# STM32G473CET6_PINOUT.net
KiCad netlist of a schematic drawn in Altium Designer
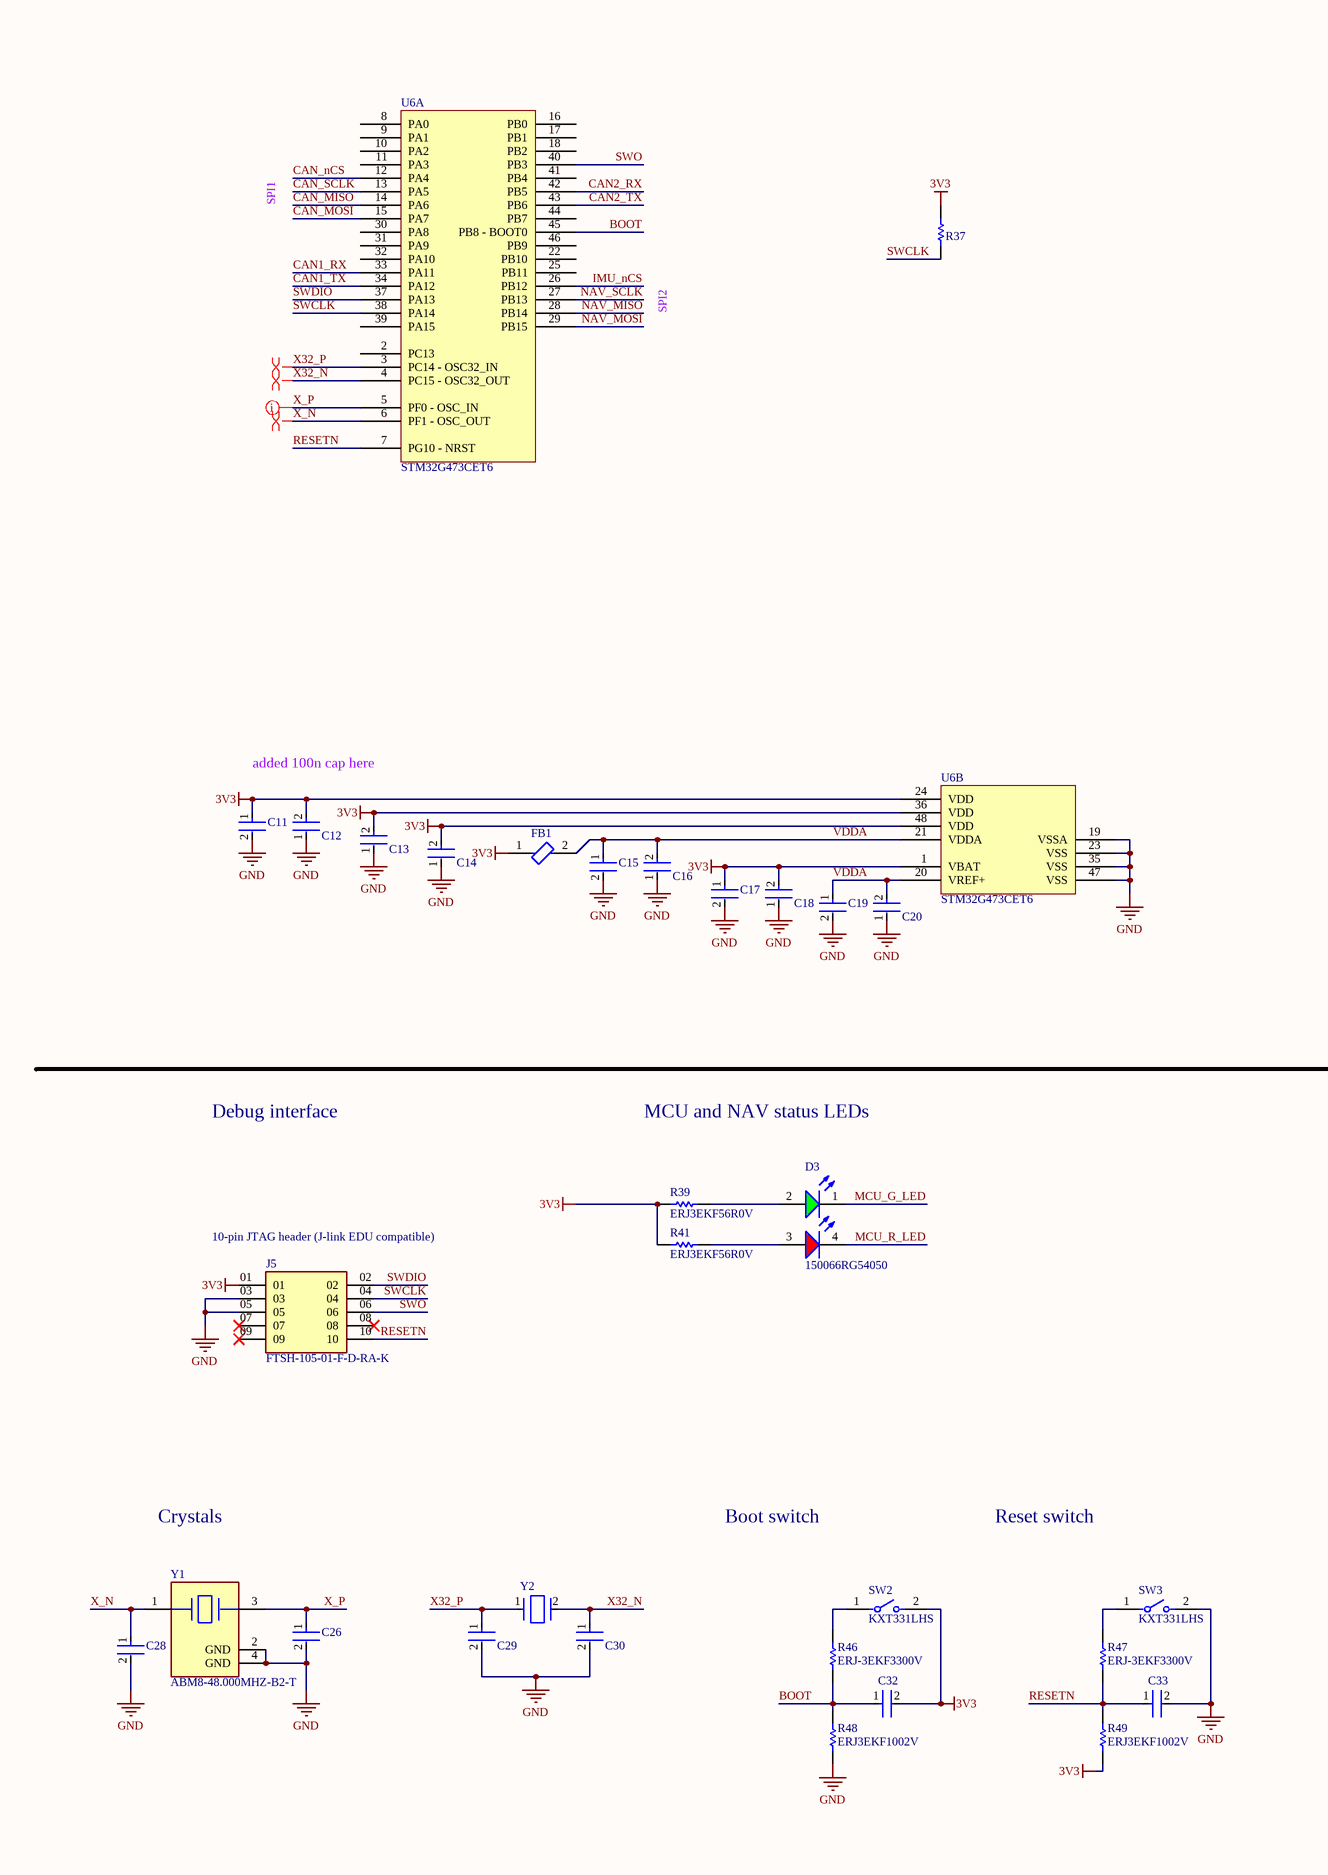
[diagram p0: STM32G473CET6_PINOUT.SchDoc, left]
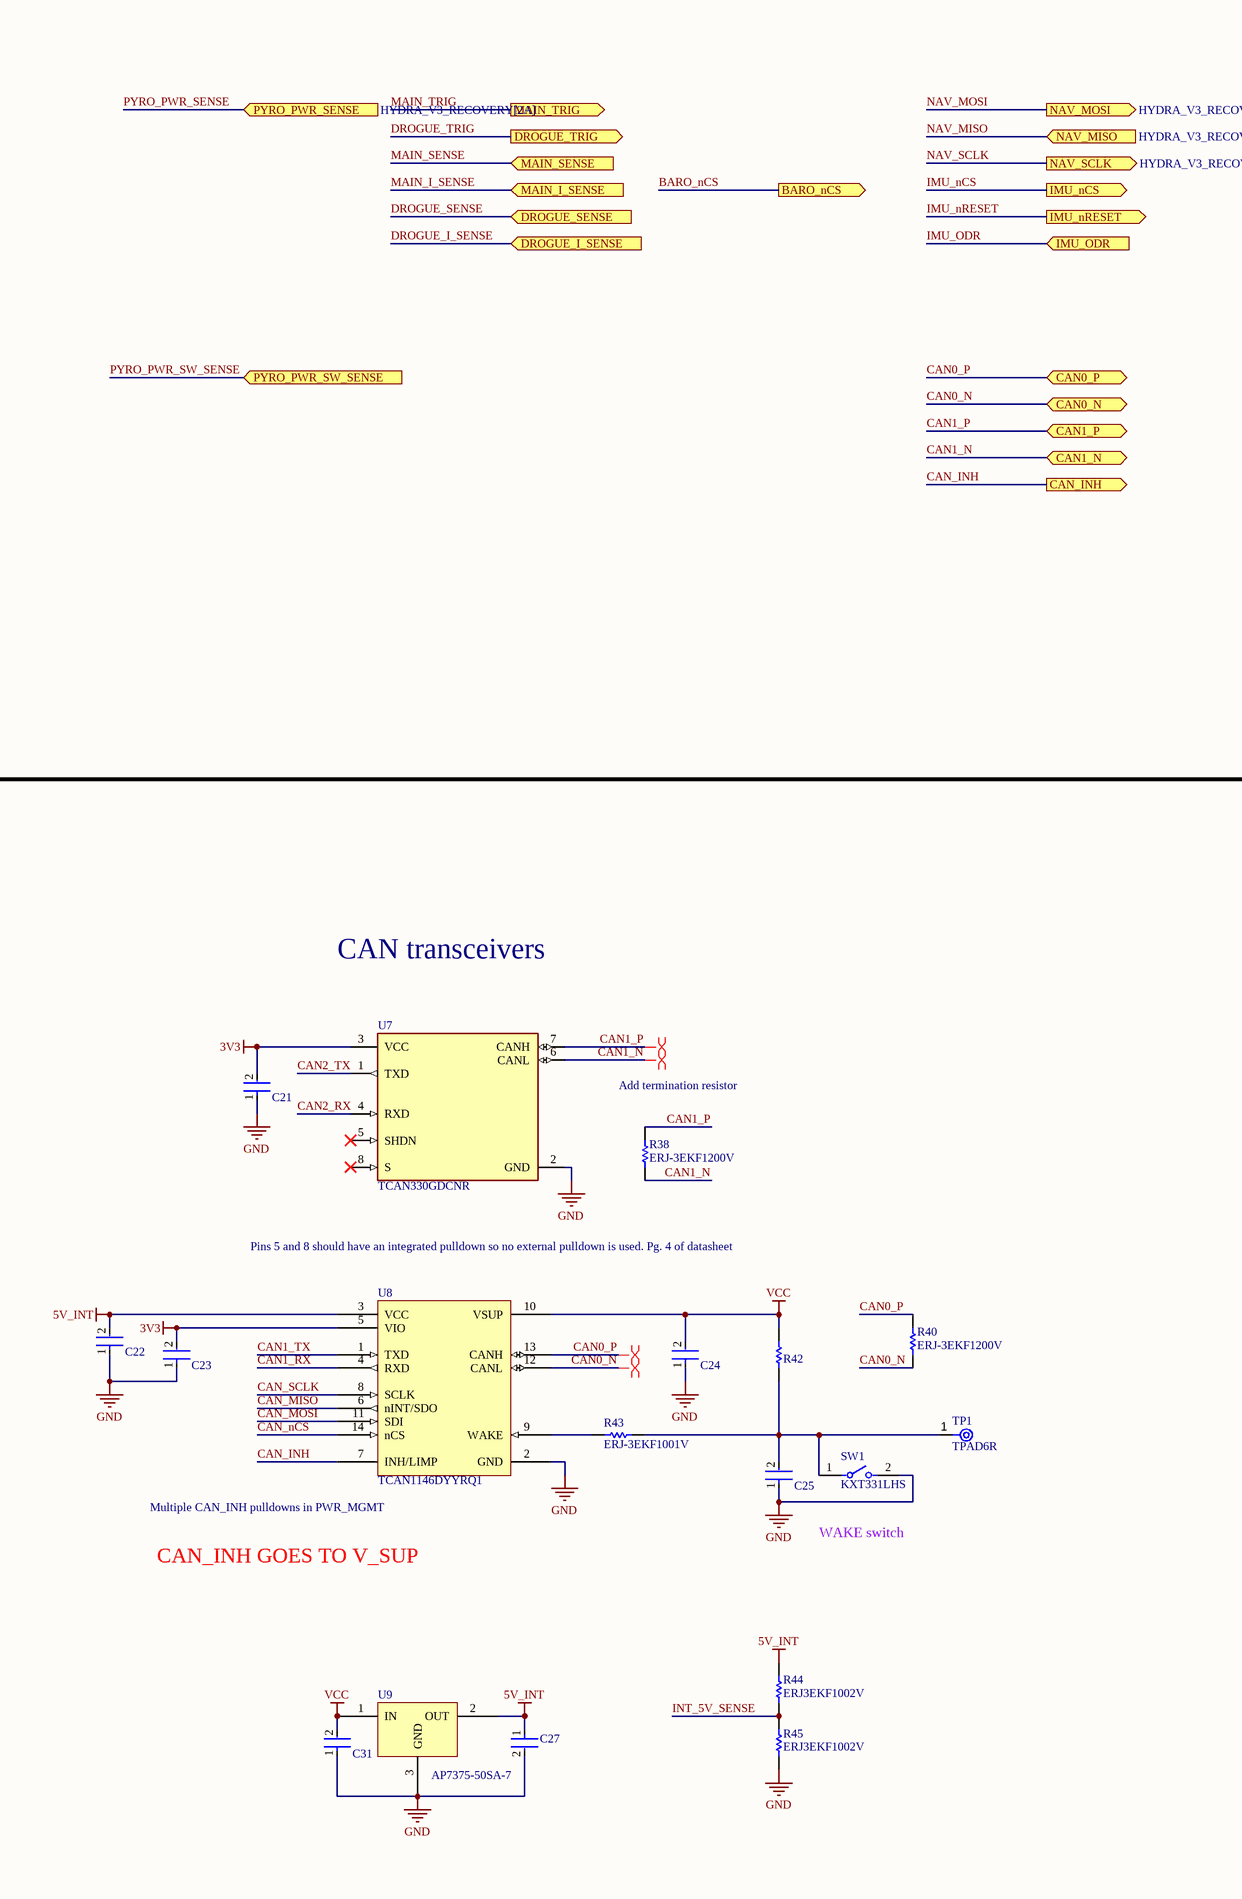
[diagram p1: STM32G473CET6_PINOUT.SchDoc, right]

(export (version "E")
  (design (tool "Eeschema 10.0.6"))
  (components
    (comp (ref "C11")
      (value "C1005X5R1A475K050BC")
      (footprint "FP-C1005-050-0_15-MFG")
      (description "CAP CER 4.7UF 10V X5R 0402")
      (fields (field (name "TOLERANCE") "10%"))
      (libsource (lib "Altium Content Vault") (part "b4654b650e69147ec39a6b967a45e02"))
    )
    (comp (ref "C12")
      (value "GRM155R71C104KA88D")
      (footprint "FP-GRM15-MFG")
      (description "CAP CER 0.1UF 16V X7R 0402")
      (fields
        (field (name "TOLERANCE") "10%")
        (field (name "OCTOPART") "https://octopart.com/grm155r71c104ka88d-murata-196880")
      )
      (libsource (lib "Altium Content Vault") (part "236180d848d6139a670b325ea6854c9"))
    )
    (comp (ref "C13")
      (value "GRM155R71C104KA88D")
      (footprint "FP-GRM15-MFG")
      (description "CAP CER 0.1UF 16V X7R 0402")
      (fields
        (field (name "TOLERANCE") "10%")
        (field (name "OCTOPART") "https://octopart.com/grm155r71c104ka88d-murata-196880")
      )
      (libsource (lib "Altium Content Vault") (part "236180d848d6139a670b325ea6854c9"))
    )
    (comp (ref "C14")
      (value "GRM155R71C104KA88D")
      (footprint "FP-GRM15-MFG")
      (description "CAP CER 0.1UF 16V X7R 0402")
      (fields
        (field (name "TOLERANCE") "10%")
        (field (name "OCTOPART") "https://octopart.com/grm155r71c104ka88d-murata-196880")
      )
      (libsource (lib "Altium Content Vault") (part "236180d848d6139a670b325ea6854c9"))
    )
    (comp (ref "C15")
      (value "EMK105BJ105KV-F")
      (footprint "FP-0402-L_1_0_0_05-W_0_5-IPC_A")
      (description "None")
      (fields (field (name "TOLERANCE") "10%"))
      (libsource (lib "Altium Content Vault") (part "b4654b650e69147ec39a6b967a45e02"))
    )
    (comp (ref "C16")
      (value "GRM155R71C104KA88D")
      (footprint "FP-GRM15-MFG")
      (description "CAP CER 0.1UF 16V X7R 0402")
      (fields
        (field (name "TOLERANCE") "10%")
        (field (name "OCTOPART") "https://octopart.com/grm155r71c104ka88d-murata-196880")
      )
      (libsource (lib "Altium Content Vault") (part "236180d848d6139a670b325ea6854c9"))
    )
    (comp (ref "C17")
      (value "EMK105BJ105KV-F")
      (footprint "FP-0402-L_1_0_0_05-W_0_5-IPC_A")
      (description "None")
      (fields (field (name "TOLERANCE") "10%"))
      (libsource (lib "Altium Content Vault") (part "b4654b650e69147ec39a6b967a45e02"))
    )
    (comp (ref "C18")
      (value "GRM155R71C104KA88D")
      (footprint "FP-GRM15-MFG")
      (description "CAP CER 0.1UF 16V X7R 0402")
      (fields
        (field (name "TOLERANCE") "10%")
        (field (name "OCTOPART") "https://octopart.com/grm155r71c104ka88d-murata-196880")
      )
      (libsource (lib "Altium Content Vault") (part "236180d848d6139a670b325ea6854c9"))
    )
    (comp (ref "C19")
      (value "EMK105BJ105KV-F")
      (footprint "FP-0402-L_1_0_0_05-W_0_5-IPC_A")
      (description "None")
      (fields (field (name "TOLERANCE") "10%"))
      (libsource (lib "Altium Content Vault") (part "b4654b650e69147ec39a6b967a45e02"))
    )
    (comp (ref "C20")
      (value "GRM155R71C104KA88D")
      (footprint "FP-GRM15-MFG")
      (description "CAP CER 0.1UF 16V X7R 0402")
      (fields
        (field (name "TOLERANCE") "10%")
        (field (name "OCTOPART") "https://octopart.com/grm155r71c104ka88d-murata-196880")
      )
      (libsource (lib "Altium Content Vault") (part "236180d848d6139a670b325ea6854c9"))
    )
    (comp (ref "C21")
      (value "C0402C104K8PACTU")
      (footprint "FP-C0402-BB-MFG")
      (description "CAP CER 0.1UF 10V X5R 0402")
      (fields (field (name "MANUFACTURER") "Kemet") (field (name "TOLERANCE") "0.1"))
      (libsource (lib "Altium Content Vault") (part "b4654b650e69147ec39a6b967a45e02"))
    )
    (comp (ref "C22")
      (value "C0402C104K8PACTU")
      (footprint "FP-C0402-BB-MFG")
      (description "CAP CER 0.1UF 10V X5R 0402")
      (fields (field (name "MANUFACTURER") "Kemet") (field (name "TOLERANCE") "0.1"))
      (libsource (lib "Altium Content Vault") (part "b4654b650e69147ec39a6b967a45e02"))
    )
    (comp (ref "C23")
      (value "C0402C104K8PACTU")
      (footprint "FP-C0402-BB-MFG")
      (description "CAP CER 0.1UF 10V X5R 0402")
      (fields (field (name "MANUFACTURER") "Kemet") (field (name "TOLERANCE") "0.1"))
      (libsource (lib "Altium Content Vault") (part "b4654b650e69147ec39a6b967a45e02"))
    )
    (comp (ref "C24")
      (value "C0402C104K8PACTU")
      (footprint "FP-C0402-BB-MFG")
      (description "CAP CER 0.1UF 10V X5R 0402")
      (fields (field (name "MANUFACTURER") "Kemet") (field (name "TOLERANCE") "0.1"))
      (libsource (lib "Altium Content Vault") (part "b4654b650e69147ec39a6b967a45e02"))
    )
    (comp (ref "C25")
      (value "C0402C104K8PACTU")
      (footprint "FP-C0402-BB-MFG")
      (description "CAP CER 0.1UF 10V X5R 0402")
      (fields (field (name "MANUFACTURER") "Kemet") (field (name "TOLERANCE") "0.1"))
      (libsource (lib "Altium Content Vault") (part "b4654b650e69147ec39a6b967a45e02"))
    )
    (comp (ref "C26")
      (value "C0402C689C5GACTU")
      (footprint "FP-C0402-BB-MFG")
      (description "CAP CER 6.8PF 50V NP0 0402")
      (fields
        (field (name "OCTOPART") "https://octopart.com/c0402c689c5gactu-kemet-9143567")
        (field (name "MANUFACTURER") "Kemet")
      )
      (libsource (lib "Altium Content Vault") (part "b4654b650e69147ec39a6b967a45e02"))
    )
    (comp (ref "C27")
      (value "CL05A106MP5NUNC")
      (footprint "FP-CL05A106MP5NUNC-MFG")
      (description "CAP CER 10UF 10V X5R 0402")
      (fields
        (field (name "OCTOPART") "https://octopart.com/cl05a106mp5nunc-samsung-22457395")
        (field (name "TOLERANCE") "20%")
      )
      (libsource (lib "Altium Content Vault") (part "b4654b650e69147ec39a6b967a45e02"))
    )
    (comp (ref "C28")
      (value "C0402C689C5GACTU")
      (footprint "FP-C0402-BB-MFG")
      (description "CAP CER 6.8PF 50V NP0 0402")
      (fields
        (field (name "OCTOPART") "https://octopart.com/c0402c689c5gactu-kemet-9143567")
        (field (name "MANUFACTURER") "Kemet")
      )
      (libsource (lib "Altium Content Vault") (part "b4654b650e69147ec39a6b967a45e02"))
    )
    (comp (ref "C29")
      (value "04025A180FAT2A")
      (footprint "FP-0402-L_1_0_1-W_0_5_0_1-IPC_A")
      (description "General Purpose Ceramic Capacitor, 0402, 18pF, 1%, C0G, 30ppm/°C, 50V")
      (fields (field (name "TOLERANCE") "1%"))
      (libsource (lib "Altium Content Vault") (part "b4654b650e69147ec39a6b967a45e02"))
    )
    (comp (ref "C30")
      (value "04025A180FAT2A")
      (footprint "FP-0402-L_1_0_1-W_0_5_0_1-IPC_A")
      (description "General Purpose Ceramic Capacitor, 0402, 18pF, 1%, C0G, 30ppm/°C, 50V")
      (fields (field (name "TOLERANCE") "1%"))
      (libsource (lib "Altium Content Vault") (part "b4654b650e69147ec39a6b967a45e02"))
    )
    (comp (ref "C31")
      (value "C0402C104K8PACTU")
      (footprint "FP-C0402-BB-MFG")
      (description "CAP CER 0.1UF 10V X5R 0402")
      (fields (field (name "MANUFACTURER") "Kemet") (field (name "TOLERANCE") "0.1"))
      (libsource (lib "Altium Content Vault") (part "b4654b650e69147ec39a6b967a45e02"))
    )
    (comp (ref "C32")
      (value "C0402C104K8PACTU")
      (footprint "FP-C0402-BB-MFG")
      (description "CAP CER 0.1UF 10V X5R 0402")
      (fields (field (name "MANUFACTURER") "Kemet") (field (name "TOLERANCE") "0.1"))
      (libsource (lib "Altium Content Vault") (part "b4654b650e69147ec39a6b967a45e02"))
    )
    (comp (ref "C33")
      (value "C0402C104K8PACTU")
      (footprint "FP-C0402-BB-MFG")
      (description "CAP CER 0.1UF 10V X5R 0402")
      (fields (field (name "MANUFACTURER") "Kemet") (field (name "TOLERANCE") "0.1"))
      (libsource (lib "Altium Content Vault") (part "b4654b650e69147ec39a6b967a45e02"))
    )
    (comp (ref "D3")
      (value "150066RG54050")
      (footprint "WL-SBCD_0606")
      (description "Led, Red/Grn, 180Mcd/230Mcd, 624Nm/525Nm Rohs Compliant: Yes")
      (fields (field (name "SOURCE") "rgled.SchLib"))
      (libsource (lib "Space Concordia") (part "CMP-004-00034-2"))
    )
    (comp (ref "FB1")
      (value "BLM15PX601SN1D")
      (footprint "FP-BLM15-0_05-MFG")
      (description "Chip Ferrite Bead, 0402, 600Ω @ 100MHz, 0.23Ω, 25%, 900mA")
      (fields (field (name "TOLERANCE") "25%"))
      (libsource (lib "Altium Content Vault") (part "5f30dd21d616792df468990f7003faa"))
    )
    (comp (ref "J5")
      (value "FTSH-105-01-F-D-RA-K")
      (footprint "FTSH-105-01-F-D-RA-K-Footprint-1")
      (libsource (lib "Space Concordia") (part "FTSH-105-01-F-D-RA-K-Symbol-1"))
    )
    (comp (ref "R37")
      (value "ERJ3EKF1002V")
      (footprint "RESC1609X55X30LL15T15")
      (description "Chip Resistor, 10 KOhm, +/- 1%, 0.1 W, -55 to 155 degC, 0603 (1608 Metric), RoHS, Tape and Reel")
      (fields (field (name "TOLERANCE") "1%") (field (name "MANUFACTURER") "Panasonic"))
      (libsource (lib "Altium Content Vault") (part "RES-2"))
    )
    (comp (ref "R38")
      (value "ERJ-3EKF1200V")
      (footprint "RESC1609X55X30ML15T15")
      (description "Chip Resistor, 120 Ohm, +/- 1%, 0.1 W, -55 to 155 degC, 0603 (1608 Metric), RoHS, Tape and Reel")
      (fields (field (name "TOLERANCE") "1%") (field (name "MANUFACTURER") "Panasonic"))
      (libsource (lib "Altium Content Vault") (part "RES-2"))
    )
    (comp (ref "R39")
      (value "ERJ3EKF56R0V")
      (footprint "RESC1608X55X30NL15T15")
      (fields (field (name "MANUFACTURER") "Panasonic"))
      (libsource (lib "Altium Content Vault") (part "RES"))
    )
    (comp (ref "R40")
      (value "ERJ-3EKF1200V")
      (footprint "RESC1609X55X30ML15T15")
      (description "Chip Resistor, 120 Ohm, +/- 1%, 0.1 W, -55 to 155 degC, 0603 (1608 Metric), RoHS, Tape and Reel")
      (fields (field (name "TOLERANCE") "1%") (field (name "MANUFACTURER") "Panasonic"))
      (libsource (lib "Altium Content Vault") (part "RES-2"))
    )
    (comp (ref "R41")
      (value "ERJ3EKF56R0V")
      (footprint "RESC1608X55X30NL15T15")
      (fields (field (name "MANUFACTURER") "Panasonic"))
      (libsource (lib "Altium Content Vault") (part "RES"))
    )
    (comp (ref "R42")
      (value "ERJ3EKF1002V")
      (footprint "RESC1609X55X30LL15T15")
      (description "Chip Resistor, 10 KOhm, +/- 1%, 0.1 W, -55 to 155 degC, 0603 (1608 Metric), RoHS, Tape and Reel")
      (fields (field (name "TOLERANCE") "1%") (field (name "MANUFACTURER") "Panasonic"))
      (libsource (lib "Altium Content Vault") (part "RES-2"))
    )
    (comp (ref "R43")
      (value "ERJ-3EKF1001V")
      (footprint "RESC1608X55X30LL15T15")
      (fields (field (name "MANUFACTURER") "Panasonic"))
      (libsource (lib "Altium Content Vault") (part "RES"))
    )
    (comp (ref "R44")
      (value "ERJ3EKF1002V")
      (footprint "RESC1609X55X30LL15T15")
      (description "Chip Resistor, 10 KOhm, +/- 1%, 0.1 W, -55 to 155 degC, 0603 (1608 Metric), RoHS, Tape and Reel")
      (fields (field (name "TOLERANCE") "1%") (field (name "MANUFACTURER") "Panasonic"))
      (libsource (lib "Altium Content Vault") (part "RES-2"))
    )
    (comp (ref "R45")
      (value "ERJ3EKF1002V")
      (footprint "RESC1609X55X30LL15T15")
      (description "Chip Resistor, 10 KOhm, +/- 1%, 0.1 W, -55 to 155 degC, 0603 (1608 Metric), RoHS, Tape and Reel")
      (fields (field (name "TOLERANCE") "1%") (field (name "MANUFACTURER") "Panasonic"))
      (libsource (lib "Altium Content Vault") (part "RES-2"))
    )
    (comp (ref "R46")
      (value "ERJ-3EKF3300V")
      (footprint "RESC1608X55X30LL15T15")
      (description "Chip Resistor, 330 Ohm, +/- 1%, 0.1 W, -55 to 155 degC, 0603 (1608 Metric), RoHS, Tape and Reel")
      (libsource (lib "Altium Content Vault") (part "RES-2"))
    )
    (comp (ref "R47")
      (value "ERJ-3EKF3300V")
      (footprint "RESC1608X55X30LL15T15")
      (description "Chip Resistor, 330 Ohm, +/- 1%, 0.1 W, -55 to 155 degC, 0603 (1608 Metric), RoHS, Tape and Reel")
      (libsource (lib "Altium Content Vault") (part "RES-2"))
    )
    (comp (ref "R48")
      (value "ERJ3EKF1002V")
      (footprint "RESC1609X55X30LL15T15")
      (description "Chip Resistor, 10 KOhm, +/- 1%, 0.1 W, -55 to 155 degC, 0603 (1608 Metric), RoHS, Tape and Reel")
      (fields (field (name "TOLERANCE") "1%") (field (name "MANUFACTURER") "Panasonic"))
      (libsource (lib "Altium Content Vault") (part "RES-2"))
    )
    (comp (ref "R49")
      (value "ERJ3EKF1002V")
      (footprint "RESC1609X55X30LL15T15")
      (description "Chip Resistor, 10 KOhm, +/- 1%, 0.1 W, -55 to 155 degC, 0603 (1608 Metric), RoHS, Tape and Reel")
      (fields (field (name "TOLERANCE") "1%") (field (name "MANUFACTURER") "Panasonic"))
      (libsource (lib "Altium Content Vault") (part "RES-2"))
    )
    (comp (ref "SW1")
      (value "KXT331LHS")
      (footprint "FP-KXT331LHS-MFG")
      (description "SWITCH TACTILE SPST-NO 0.02A 15V")
      (libsource (lib "Altium Content Vault") (part "bb27bde45df87f1f469753f287ef5ae"))
    )
    (comp (ref "SW2")
      (value "KXT331LHS")
      (footprint "FP-KXT331LHS-MFG")
      (description "SWITCH TACTILE SPST-NO 0.02A 15V")
      (libsource (lib "Altium Content Vault") (part "bb27bde45df87f1f469753f287ef5ae"))
    )
    (comp (ref "SW3")
      (value "KXT331LHS")
      (footprint "FP-KXT331LHS-MFG")
      (description "SWITCH TACTILE SPST-NO 0.02A 15V")
      (libsource (lib "Altium Content Vault") (part "bb27bde45df87f1f469753f287ef5ae"))
    )
    (comp (ref "TP1")
      (value "TPAD6R")
      (footprint "New footprint 1")
      (description "Test Point .6mm")
      (libsource (lib "Space Concordia") (part "TP"))
    )
    (comp (ref "U6")
      (value "STM32G473CET6")
      (footprint "TSQFP50P900X900X160-48N")
      (description "RISC Microcontroller, 32-Bit, 170MHz")
      (libsource (lib "Space Concordia") (part "STM32G473CET6"))
    )
    (comp (ref "U7")
      (value "TCAN330GDCNR")
      (footprint "FP-DCN0008A-MFG")
      (description "IC TRANSCEIVER 1/1 SOT23-8")
      (libsource (lib "Altium Content Vault") (part "22681b49c22ad38c6a4e12e04c36c7a"))
    )
    (comp (ref "U8")
      (value "TCAN1146DYYRQ1")
      (footprint "TCAN1146DYYRQ1-Footprint-1")
      (libsource (lib "Space Concordia") (part "CMP-015-00012-2"))
    )
    (comp (ref "U9")
      (value "AP7375-50SA-7")
      (footprint "AP7375-50SA-7-Footprint-1")
      (description "Ldo Cmos Lowcurr SOT23 T&r 3K")
      (libsource (lib "Space Concordia") (part "AP7375-50SA-7"))
    )
    (comp (ref "Y1")
      (value "ABM8-48.000MHZ-B2-T")
      (footprint "FP-ABM8-MFG")
      (description "Crystal 48MHz ±20ppm 18pF SMD-4 3.2mm x 2.5mm")
      (fields (field (name "TOLERANCE") "20ppm"))
      (libsource (lib "Altium Content Vault") (part "dfdb7f9a12507849fb681da9a70121c"))
    )
    (comp (ref "Y2")
      (value "ECS-.327-12.5-1210-TR")
      (footprint "FP-ECX-1210-MFG")
      (description "CRYSTAL 32.7680KHZ 12.5PF SMD")
      (fields
        (field (name "OCTOPART") "https://octopart.com/ecs-.327-12.5-1210-tr-ecs+international-81221340")
        (field (name "TOLERANCE") "20ppm")
      )
      (libsource (lib "Altium Content Vault") (part "99724985039315a44fd0d1401b84e49"))
    )
  )
  (nets
    (net (code "2") (name "/BOOT") (class "Default")
      (node (ref "C32") (pin "1") (pinfunction "1_1") (pintype "passive"))
      (node (ref "R46") (pin "1") (pinfunction "1_1") (pintype "passive"))
      (node (ref "R48") (pin "2") (pinfunction "2_2") (pintype "passive"))
      (node (ref "U6") (pin "45") (pinfunction "PB8_-_BOOT0_45") (pintype "passive"))
    )
    (net (code "3") (name "/CAN0_N") (class "Default")
      (node (ref "R40") (pin "2") (pinfunction "2_2") (pintype "passive"))
      (node (ref "U8") (pin "12") (pinfunction "CANL_12") (pintype "bidirectional"))
    )
    (net (code "4") (name "/CAN0_P") (class "Default")
      (node (ref "R40") (pin "1") (pinfunction "1_1") (pintype "passive"))
      (node (ref "U8") (pin "13") (pinfunction "CANH_13") (pintype "bidirectional"))
    )
    (net (code "5") (name "/CAN1_N") (class "Default")
      (node (ref "R38") (pin "1") (pinfunction "1_1") (pintype "passive"))
      (node (ref "U7") (pin "6") (pinfunction "CANL_6") (pintype "bidirectional"))
    )
    (net (code "6") (name "/CAN1_P") (class "Default")
      (node (ref "R38") (pin "2") (pinfunction "2_2") (pintype "passive"))
      (node (ref "U7") (pin "7") (pinfunction "CANH_7") (pintype "bidirectional"))
    )
    (net (code "7") (name "/CAN1_RX") (class "Default")
      (node (ref "U6") (pin "33") (pinfunction "PA11_33") (pintype "passive"))
      (node (ref "U8") (pin "4") (pinfunction "RXD_4") (pintype "output"))
    )
    (net (code "8") (name "/CAN1_TX") (class "Default")
      (node (ref "U6") (pin "34") (pinfunction "PA12_34") (pintype "passive"))
      (node (ref "U8") (pin "1") (pinfunction "TXD_1") (pintype "input"))
    )
    (net (code "9") (name "/CAN2_RX") (class "Default")
      (node (ref "U6") (pin "42") (pinfunction "PB5_42") (pintype "passive"))
      (node (ref "U7") (pin "4") (pinfunction "RXD_4") (pintype "input"))
    )
    (net (code "10") (name "/CAN2_TX") (class "Default")
      (node (ref "U6") (pin "43") (pinfunction "PB6_43") (pintype "passive"))
      (node (ref "U7") (pin "1") (pinfunction "TXD_1") (pintype "output"))
    )
    (net (code "11") (name "/CAN_INH") (class "Default")
      (node (ref "U8") (pin "7") (pinfunction "INH/LIMP_7") (pintype "passive"))
    )
    (net (code "12") (name "/CAN_MISO") (class "Default")
      (node (ref "U6") (pin "14") (pinfunction "PA6_14") (pintype "passive"))
      (node (ref "U8") (pin "6") (pinfunction "nINT/SDO_6") (pintype "output"))
    )
    (net (code "13") (name "/CAN_MOSI") (class "Default")
      (node (ref "U6") (pin "15") (pinfunction "PA7_15") (pintype "passive"))
      (node (ref "U8") (pin "11") (pinfunction "SDI_11") (pintype "input"))
    )
    (net (code "14") (name "/CAN_SCLK") (class "Default")
      (node (ref "U6") (pin "13") (pinfunction "PA5_13") (pintype "passive"))
      (node (ref "U8") (pin "8") (pinfunction "SCLK_8") (pintype "input"))
    )
    (net (code "15") (name "/CAN_nCS") (class "Default")
      (node (ref "U6") (pin "12") (pinfunction "PA4_12") (pintype "passive"))
      (node (ref "U8") (pin "14") (pinfunction "nCS_14") (pintype "input"))
    )
    (net (code "20") (name "/IMU_nCS") (class "Default")
      (node (ref "U6") (pin "26") (pinfunction "PB12_26") (pintype "passive"))
    )
    (net (code "22") (name "/INT_5V_SENSE") (class "Default")
      (node (ref "R44") (pin "1") (pinfunction "1_1") (pintype "passive"))
      (node (ref "R45") (pin "1") (pinfunction "1_1") (pintype "passive"))
    )
    (net (code "26") (name "/MCU_G_LED") (class "Default")
      (node (ref "D3") (pin "1") (pinfunction "K_1") (pintype "passive"))
    )
    (net (code "27") (name "/MCU_R_LED") (class "Default")
      (node (ref "D3") (pin "4") (pinfunction "K_4") (pintype "passive"))
    )
    (net (code "28") (name "/NAV_MISO") (class "Default")
      (node (ref "U6") (pin "28") (pinfunction "PB14_28") (pintype "passive"))
    )
    (net (code "29") (name "/NAV_MOSI") (class "Default")
      (node (ref "U6") (pin "29") (pinfunction "PB15_29") (pintype "passive"))
    )
    (net (code "30") (name "/NAV_SCLK") (class "Default")
      (node (ref "U6") (pin "27") (pinfunction "PB13_27") (pintype "passive"))
    )
    (net (code "33") (name "/RESETN") (class "Default")
      (node (ref "C33") (pin "1") (pinfunction "1_1") (pintype "passive"))
      (node (ref "J5") (pin "10") (pinfunction "10_10") (pintype "passive"))
      (node (ref "R47") (pin "1") (pinfunction "1_1") (pintype "passive"))
      (node (ref "R49") (pin "2") (pinfunction "2_2") (pintype "passive"))
      (node (ref "U6") (pin "7") (pinfunction "PG10_-_NRST_7") (pintype "passive"))
    )
    (net (code "34") (name "/SWCLK") (class "Default")
      (node (ref "J5") (pin "04") (pinfunction "04_04") (pintype "passive"))
      (node (ref "R37") (pin "2") (pinfunction "2_2") (pintype "passive"))
      (node (ref "U6") (pin "38") (pinfunction "PA14_38") (pintype "passive"))
    )
    (net (code "35") (name "/SWDIO") (class "Default")
      (node (ref "J5") (pin "02") (pinfunction "02_02") (pintype "passive"))
      (node (ref "U6") (pin "37") (pinfunction "PA13_37") (pintype "passive"))
    )
    (net (code "36") (name "/SWO") (class "Default")
      (node (ref "J5") (pin "06") (pinfunction "06_06") (pintype "passive"))
      (node (ref "U6") (pin "40") (pinfunction "PB3_40") (pintype "passive"))
    )
    (net (code "37") (name "/VDDA") (class "Default")
      (node (ref "C15") (pin "1") (pinfunction "1_1") (pintype "passive"))
      (node (ref "C16") (pin "2") (pinfunction "2_2") (pintype "passive"))
      (node (ref "C19") (pin "1") (pinfunction "1_1") (pintype "passive"))
      (node (ref "C20") (pin "2") (pinfunction "2_2") (pintype "passive"))
      (node (ref "FB1") (pin "2") (pinfunction "2_2") (pintype "passive"))
      (node (ref "U6") (pin "20") (pinfunction "VREF+_20") (pintype "passive"))
      (node (ref "U6") (pin "21") (pinfunction "VDDA_21") (pintype "passive"))
    )
    (net (code "38") (name "/X32_N") (class "Default")
      (node (ref "C30") (pin "1") (pinfunction "1_1") (pintype "passive"))
      (node (ref "U6") (pin "4") (pinfunction "PC15_-_OSC32_OUT_4") (pintype "passive"))
      (node (ref "Y2") (pin "2") (pinfunction "Out/In_2") (pintype "passive"))
    )
    (net (code "39") (name "/X32_P") (class "Default")
      (node (ref "C29") (pin "1") (pinfunction "1_1") (pintype "passive"))
      (node (ref "U6") (pin "3") (pinfunction "PC14_-_OSC32_IN_3") (pintype "passive"))
      (node (ref "Y2") (pin "1") (pinfunction "In/Out_1") (pintype "passive"))
    )
    (net (code "40") (name "/X_N") (class "Default")
      (node (ref "C28") (pin "1") (pinfunction "1_1") (pintype "passive"))
      (node (ref "U6") (pin "6") (pinfunction "PF1_-_OSC_OUT_6") (pintype "passive"))
      (node (ref "Y1") (pin "1") (pinfunction "1_1") (pintype "passive"))
    )
    (net (code "41") (name "/X_P") (class "Default")
      (node (ref "C26") (pin "1") (pinfunction "1_1") (pintype "passive"))
      (node (ref "U6") (pin "5") (pinfunction "PF0_-_OSC_IN_5") (pintype "passive"))
      (node (ref "Y1") (pin "3") (pinfunction "3_3") (pintype "passive"))
    )
    (net (code "42") (name "3V3") (class "Default")
      (node (ref "C11") (pin "1") (pinfunction "1_1") (pintype "passive"))
      (node (ref "C12") (pin "2") (pinfunction "2_2") (pintype "passive"))
      (node (ref "C13") (pin "2") (pinfunction "2_2") (pintype "passive"))
      (node (ref "C14") (pin "2") (pinfunction "2_2") (pintype "passive"))
      (node (ref "C17") (pin "1") (pinfunction "1_1") (pintype "passive"))
      (node (ref "C18") (pin "2") (pinfunction "2_2") (pintype "passive"))
      (node (ref "C21") (pin "2") (pinfunction "2_2") (pintype "passive"))
      (node (ref "C23") (pin "2") (pinfunction "2_2") (pintype "passive"))
      (node (ref "C32") (pin "2") (pinfunction "2_2") (pintype "passive"))
      (node (ref "FB1") (pin "1") (pinfunction "1_1") (pintype "passive"))
      (node (ref "J5") (pin "01") (pinfunction "01_01") (pintype "passive"))
      (node (ref "R37") (pin "1") (pinfunction "1_1") (pintype "passive"))
      (node (ref "R39") (pin "2") (pinfunction "2_2") (pintype "passive"))
      (node (ref "R41") (pin "2") (pinfunction "2_2") (pintype "passive"))
      (node (ref "R49") (pin "1") (pinfunction "1_1") (pintype "passive"))
      (node (ref "SW2") (pin "2") (pinfunction "2_2") (pintype "passive"))
      (node (ref "U6") (pin "1") (pinfunction "VBAT_1") (pintype "passive"))
      (node (ref "U6") (pin "24") (pinfunction "VDD_24") (pintype "passive"))
      (node (ref "U6") (pin "36") (pinfunction "VDD_36") (pintype "passive"))
      (node (ref "U6") (pin "48") (pinfunction "VDD_48") (pintype "passive"))
      (node (ref "U7") (pin "3") (pinfunction "VCC_3") (pintype "power_in"))
      (node (ref "U8") (pin "5") (pinfunction "VIO_5") (pintype "power_in"))
    )
    (net (code "43") (name "5V_INT") (class "Default")
      (node (ref "C22") (pin "2") (pinfunction "2_2") (pintype "passive"))
      (node (ref "C27") (pin "1") (pinfunction "1_1") (pintype "passive"))
      (node (ref "R44") (pin "2") (pinfunction "2_2") (pintype "passive"))
      (node (ref "U8") (pin "3") (pinfunction "VCC_3") (pintype "power_in"))
      (node (ref "U9") (pin "2") (pinfunction "OUT_2") (pintype "passive"))
    )
    (net (code "44") (name "GND") (class "Default")
      (node (ref "C11") (pin "2") (pinfunction "2_2") (pintype "passive"))
      (node (ref "C12") (pin "1") (pinfunction "1_1") (pintype "passive"))
      (node (ref "C13") (pin "1") (pinfunction "1_1") (pintype "passive"))
      (node (ref "C14") (pin "1") (pinfunction "1_1") (pintype "passive"))
      (node (ref "C15") (pin "2") (pinfunction "2_2") (pintype "passive"))
      (node (ref "C16") (pin "1") (pinfunction "1_1") (pintype "passive"))
      (node (ref "C17") (pin "2") (pinfunction "2_2") (pintype "passive"))
      (node (ref "C18") (pin "1") (pinfunction "1_1") (pintype "passive"))
      (node (ref "C19") (pin "2") (pinfunction "2_2") (pintype "passive"))
      (node (ref "C20") (pin "1") (pinfunction "1_1") (pintype "passive"))
      (node (ref "C21") (pin "1") (pinfunction "1_1") (pintype "passive"))
      (node (ref "C22") (pin "1") (pinfunction "1_1") (pintype "passive"))
      (node (ref "C23") (pin "1") (pinfunction "1_1") (pintype "passive"))
      (node (ref "C24") (pin "1") (pinfunction "1_1") (pintype "passive"))
      (node (ref "C25") (pin "1") (pinfunction "1_1") (pintype "passive"))
      (node (ref "C26") (pin "2") (pinfunction "2_2") (pintype "passive"))
      (node (ref "C27") (pin "2") (pinfunction "2_2") (pintype "passive"))
      (node (ref "C28") (pin "2") (pinfunction "2_2") (pintype "passive"))
      (node (ref "C29") (pin "2") (pinfunction "2_2") (pintype "passive"))
      (node (ref "C30") (pin "2") (pinfunction "2_2") (pintype "passive"))
      (node (ref "C31") (pin "1") (pinfunction "1_1") (pintype "passive"))
      (node (ref "C33") (pin "2") (pinfunction "2_2") (pintype "passive"))
      (node (ref "J5") (pin "03") (pinfunction "03_03") (pintype "passive"))
      (node (ref "J5") (pin "05") (pinfunction "05_05") (pintype "passive"))
      (node (ref "R45") (pin "2") (pinfunction "2_2") (pintype "passive"))
      (node (ref "R48") (pin "1") (pinfunction "1_1") (pintype "passive"))
      (node (ref "SW1") (pin "2") (pinfunction "2_2") (pintype "passive"))
      (node (ref "SW3") (pin "2") (pinfunction "2_2") (pintype "passive"))
      (node (ref "U6") (pin "19") (pinfunction "VSSA_19") (pintype "passive"))
      (node (ref "U6") (pin "23") (pinfunction "VSS_23") (pintype "passive"))
      (node (ref "U6") (pin "35") (pinfunction "VSS_35") (pintype "passive"))
      (node (ref "U6") (pin "47") (pinfunction "VSS_47") (pintype "passive"))
      (node (ref "U7") (pin "2") (pinfunction "GND_2") (pintype "power_in"))
      (node (ref "U8") (pin "2") (pinfunction "GND_2") (pintype "power_in"))
      (node (ref "U9") (pin "3") (pinfunction "GND_3") (pintype "passive"))
      (node (ref "Y1") (pin "2") (pinfunction "GND_2") (pintype "power_in"))
      (node (ref "Y1") (pin "4") (pinfunction "GND_4") (pintype "power_in"))
    )
    (net (code "45") (name "Net-(D3-A-Pad2)") (class "Default")
      (node (ref "D3") (pin "2") (pinfunction "A_2") (pintype "passive"))
      (node (ref "R39") (pin "1") (pinfunction "1_1") (pintype "passive"))
    )
    (net (code "46") (name "Net-(D3-A-Pad3)") (class "Default")
      (node (ref "D3") (pin "3") (pinfunction "A_3") (pintype "passive"))
      (node (ref "R41") (pin "1") (pinfunction "1_1") (pintype "passive"))
    )
    (net (code "47") (name "Net-(R46-Pad2)") (class "Default")
      (node (ref "R46") (pin "2") (pinfunction "2_2") (pintype "passive"))
      (node (ref "SW2") (pin "1") (pinfunction "1_1") (pintype "passive"))
    )
    (net (code "48") (name "Net-(R47-Pad2)") (class "Default")
      (node (ref "R47") (pin "2") (pinfunction "2_2") (pintype "passive"))
      (node (ref "SW3") (pin "1") (pinfunction "1_1") (pintype "passive"))
    )
    (net (code "49") (name "Net-(TP1-TP)") (class "Default")
      (node (ref "C25") (pin "2") (pinfunction "2_2") (pintype "passive"))
      (node (ref "R42") (pin "2") (pinfunction "2_2") (pintype "passive"))
      (node (ref "R43") (pin "2") (pinfunction "2_2") (pintype "passive"))
      (node (ref "SW1") (pin "1") (pinfunction "1_1") (pintype "passive"))
      (node (ref "TP1") (pin "1") (pinfunction "TP_1") (pintype "passive"))
    )
    (net (code "50") (name "Net-(U8-WAKE)") (class "Default")
      (node (ref "R43") (pin "1") (pinfunction "1_1") (pintype "passive"))
      (node (ref "U8") (pin "9") (pinfunction "WAKE_9") (pintype "input"))
    )
    (net (code "51") (name "VCC") (class "Default")
      (node (ref "C24") (pin "2") (pinfunction "2_2") (pintype "passive"))
      (node (ref "C31") (pin "2") (pinfunction "2_2") (pintype "passive"))
      (node (ref "R42") (pin "1") (pinfunction "1_1") (pintype "passive"))
      (node (ref "U8") (pin "10") (pinfunction "VSUP_10") (pintype "power_in"))
      (node (ref "U9") (pin "1") (pinfunction "IN_1") (pintype "passive"))
    )
    (net (code "52") (name "unconnected-(J5-Pad07)") (class "Default")
      (node (ref "J5") (pin "07") (pinfunction "07_07") (pintype "passive+no_connect"))
    )
    (net (code "53") (name "unconnected-(J5-Pad08)") (class "Default")
      (node (ref "J5") (pin "08") (pinfunction "08_08") (pintype "passive+no_connect"))
    )
    (net (code "54") (name "unconnected-(J5-Pad09)") (class "Default")
      (node (ref "J5") (pin "09") (pinfunction "09_09") (pintype "passive+no_connect"))
    )
    (net (code "55") (name "unconnected-(U6A-PA0-Pad8)") (class "Default")
      (node (ref "U6") (pin "8") (pinfunction "PA0_8") (pintype "passive"))
    )
    (net (code "56") (name "unconnected-(U6A-PA1-Pad9)") (class "Default")
      (node (ref "U6") (pin "9") (pinfunction "PA1_9") (pintype "passive"))
    )
    (net (code "57") (name "unconnected-(U6A-PA2-Pad10)") (class "Default")
      (node (ref "U6") (pin "10") (pinfunction "PA2_10") (pintype "passive"))
    )
    (net (code "58") (name "unconnected-(U6A-PA3-Pad11)") (class "Default")
      (node (ref "U6") (pin "11") (pinfunction "PA3_11") (pintype "passive"))
    )
    (net (code "59") (name "unconnected-(U6A-PA8-Pad30)") (class "Default")
      (node (ref "U6") (pin "30") (pinfunction "PA8_30") (pintype "passive"))
    )
    (net (code "60") (name "unconnected-(U6A-PA9-Pad31)") (class "Default")
      (node (ref "U6") (pin "31") (pinfunction "PA9_31") (pintype "passive"))
    )
    (net (code "61") (name "unconnected-(U6A-PA10-Pad32)") (class "Default")
      (node (ref "U6") (pin "32") (pinfunction "PA10_32") (pintype "passive"))
    )
    (net (code "62") (name "unconnected-(U6A-PA15-Pad39)") (class "Default")
      (node (ref "U6") (pin "39") (pinfunction "PA15_39") (pintype "passive"))
    )
    (net (code "63") (name "unconnected-(U6A-PB0-Pad16)") (class "Default")
      (node (ref "U6") (pin "16") (pinfunction "PB0_16") (pintype "passive"))
    )
    (net (code "64") (name "unconnected-(U6A-PB1-Pad17)") (class "Default")
      (node (ref "U6") (pin "17") (pinfunction "PB1_17") (pintype "passive"))
    )
    (net (code "65") (name "unconnected-(U6A-PB2-Pad18)") (class "Default")
      (node (ref "U6") (pin "18") (pinfunction "PB2_18") (pintype "passive"))
    )
    (net (code "66") (name "unconnected-(U6A-PB4-Pad41)") (class "Default")
      (node (ref "U6") (pin "41") (pinfunction "PB4_41") (pintype "passive"))
    )
    (net (code "67") (name "unconnected-(U6A-PB7-Pad44)") (class "Default")
      (node (ref "U6") (pin "44") (pinfunction "PB7_44") (pintype "passive"))
    )
    (net (code "68") (name "unconnected-(U6A-PB9-Pad46)") (class "Default")
      (node (ref "U6") (pin "46") (pinfunction "PB9_46") (pintype "passive"))
    )
    (net (code "69") (name "unconnected-(U6A-PB10-Pad22)") (class "Default")
      (node (ref "U6") (pin "22") (pinfunction "PB10_22") (pintype "passive"))
    )
    (net (code "70") (name "unconnected-(U6A-PB11-Pad25)") (class "Default")
      (node (ref "U6") (pin "25") (pinfunction "PB11_25") (pintype "passive"))
    )
    (net (code "71") (name "unconnected-(U6A-PC13-Pad2)") (class "Default")
      (node (ref "U6") (pin "2") (pinfunction "PC13_2") (pintype "passive"))
    )
    (net (code "72") (name "unconnected-(U7-S-Pad8)") (class "Default")
      (node (ref "U7") (pin "8") (pinfunction "S_8") (pintype "input+no_connect"))
    )
    (net (code "73") (name "unconnected-(U7-SHDN-Pad5)") (class "Default")
      (node (ref "U7") (pin "5") (pinfunction "SHDN_5") (pintype "input+no_connect"))
    )
  )
)
